# 50_VOLTAGE_FRONTEND.net
KiCad netlist of a schematic drawn in Altium Designer
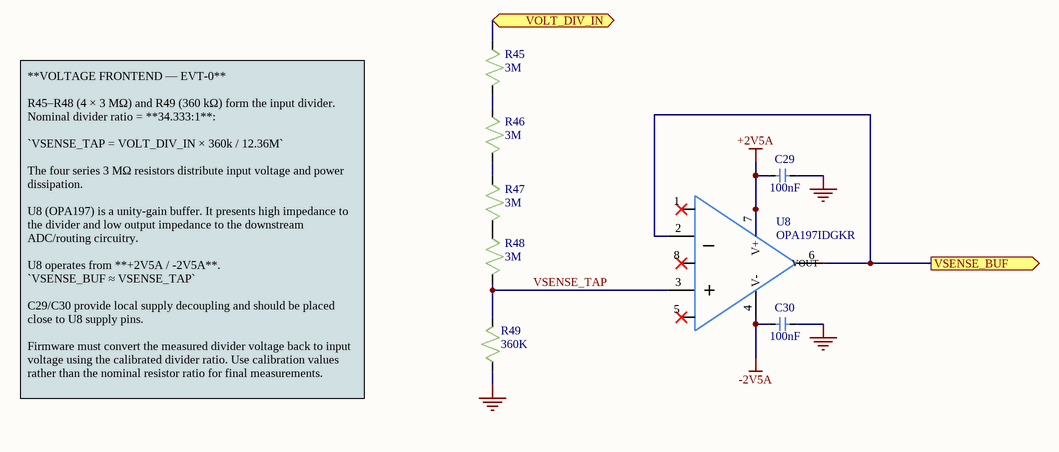
[diagram p0: 50_VOLTAGE_FRONTEND.SchDoc]

(export (version "E")
  (design (tool "Eeschema 10.0.6"))
  (components
    (comp (ref "C29")
      (value "100nF")
      (footprint "C0805")
      (libsource (lib "PocketLab_DMM_EVT0") (part "C_0805"))
    )
    (comp (ref "C30")
      (value "100nF")
      (footprint "C0805")
      (libsource (lib "PocketLab_DMM_EVT0") (part "C_0805"))
    )
    (comp (ref "R45")
      (value "3M")
      (footprint "R1206")
      (description "RES 3M OHM 0.1% 1/4W 1206")
      (fields
        (field (name "MANUFACTURER") "Susumu")
        (field (name "MANUFACTURER PART NUMBER") "RGV3216P-3004-B-T1")
      )
      (libsource (lib "PocketLab_DMM_SchLib") (part "RGV3216P-3004-B-T1"))
    )
    (comp (ref "R46")
      (value "3M")
      (footprint "R1206")
      (description "RES 3M OHM 0.1% 1/4W 1206")
      (fields
        (field (name "MANUFACTURER") "Susumu")
        (field (name "MANUFACTURER PART NUMBER") "RGV3216P-3004-B-T1")
      )
      (libsource (lib "PocketLab_DMM_SchLib") (part "RGV3216P-3004-B-T1"))
    )
    (comp (ref "R47")
      (value "3M")
      (footprint "R1206")
      (description "RES 3M OHM 0.1% 1/4W 1206")
      (fields
        (field (name "MANUFACTURER") "Susumu")
        (field (name "MANUFACTURER PART NUMBER") "RGV3216P-3004-B-T1")
      )
      (libsource (lib "PocketLab_DMM_SchLib") (part "RGV3216P-3004-B-T1"))
    )
    (comp (ref "R48")
      (value "3M")
      (footprint "R1206")
      (description "RES 3M OHM 0.1% 1/4W 1206")
      (fields
        (field (name "MANUFACTURER") "Susumu")
        (field (name "MANUFACTURER PART NUMBER") "RGV3216P-3004-B-T1")
      )
      (libsource (lib "PocketLab_DMM_SchLib") (part "RGV3216P-3004-B-T1"))
    )
    (comp (ref "R49")
      (value "360K")
      (footprint "R1206")
      (description "RES 360K OHM 0.1% 1/4W 1206")
      (fields
        (field (name "MANUFACTURER") "Susumu")
        (field (name "MANUFACTURER PART NUMBER") "RGV3216P-3603-B-T1")
      )
      (libsource (lib "PocketLab_DMM_EVT0") (part "RGV3216P-3603-B-T1"))
    )
    (comp (ref "U8")
      (value "OPA197IDGKR")
      (footprint "OPA197IDGKR")
      (description "Precision rail-to-rail operational amplifier")
      (fields (field (name "MANUFACTURER") "Texas Instruments"))
      (libsource (lib "PocketLab_DMM_EVT0") (part "OPA197IDGKR"))
    )
  )
  (nets
    (net (code "1") (name "+2V5A") (class "Default")
      (node (ref "C29") (pin "1") (pinfunction "1_1") (pintype "passive"))
      (node (ref "U8") (pin "7") (pinfunction "V+_7") (pintype "passive"))
    )
    (net (code "2") (name "-2V5A") (class "Default")
      (node (ref "C30") (pin "1") (pinfunction "1_1") (pintype "passive"))
      (node (ref "U8") (pin "4") (pinfunction "V-_4") (pintype "passive"))
    )
    (net (code "3") (name "/VOLT_DIV_IN") (class "Default")
      (node (ref "R45") (pin "1") (pinfunction "1_1") (pintype "passive"))
    )
    (net (code "4") (name "/VSENSE_BUF") (class "Default")
      (node (ref "U8") (pin "2") (pinfunction "__2") (pintype "passive"))
      (node (ref "U8") (pin "6") (pinfunction "VOUT_6") (pintype "passive"))
    )
    (net (code "5") (name "/VSENSE_TAP") (class "Default")
      (node (ref "R48") (pin "2") (pinfunction "2_2") (pintype "passive"))
      (node (ref "R49") (pin "2") (pinfunction "2_2") (pintype "passive"))
      (node (ref "U8") (pin "3") (pinfunction "+_3") (pintype "passive"))
    )
    (net (code "6") (name "GND") (class "Default")
      (node (ref "C29") (pin "2") (pinfunction "2_2") (pintype "passive"))
      (node (ref "C30") (pin "2") (pinfunction "2_2") (pintype "passive"))
      (node (ref "R49") (pin "1") (pinfunction "1_1") (pintype "passive"))
    )
    (net (code "7") (name "Net-(R45-Pad2)") (class "Default")
      (node (ref "R45") (pin "2") (pinfunction "2_2") (pintype "passive"))
      (node (ref "R46") (pin "1") (pinfunction "1_1") (pintype "passive"))
    )
    (net (code "8") (name "Net-(R46-Pad2)") (class "Default")
      (node (ref "R46") (pin "2") (pinfunction "2_2") (pintype "passive"))
      (node (ref "R47") (pin "1") (pinfunction "1_1") (pintype "passive"))
    )
    (net (code "9") (name "Net-(R47-Pad2)") (class "Default")
      (node (ref "R47") (pin "2") (pinfunction "2_2") (pintype "passive"))
      (node (ref "R48") (pin "1") (pinfunction "1_1") (pintype "passive"))
    )
    (net (code "10") (name "unconnected-(U8-Pad1)") (class "Default")
      (node (ref "U8") (pin "1") (pinfunction "1_1") (pintype "passive+no_connect"))
    )
    (net (code "11") (name "unconnected-(U8-Pad5)") (class "Default")
      (node (ref "U8") (pin "5") (pinfunction "5_5") (pintype "passive+no_connect"))
    )
    (net (code "12") (name "unconnected-(U8-Pad8)") (class "Default")
      (node (ref "U8") (pin "8") (pinfunction "8_8") (pintype "passive+no_connect"))
    )
  )
)
